# DIOT_signal_routing.net
KiCad netlist of a schematic drawn in Altium Designer
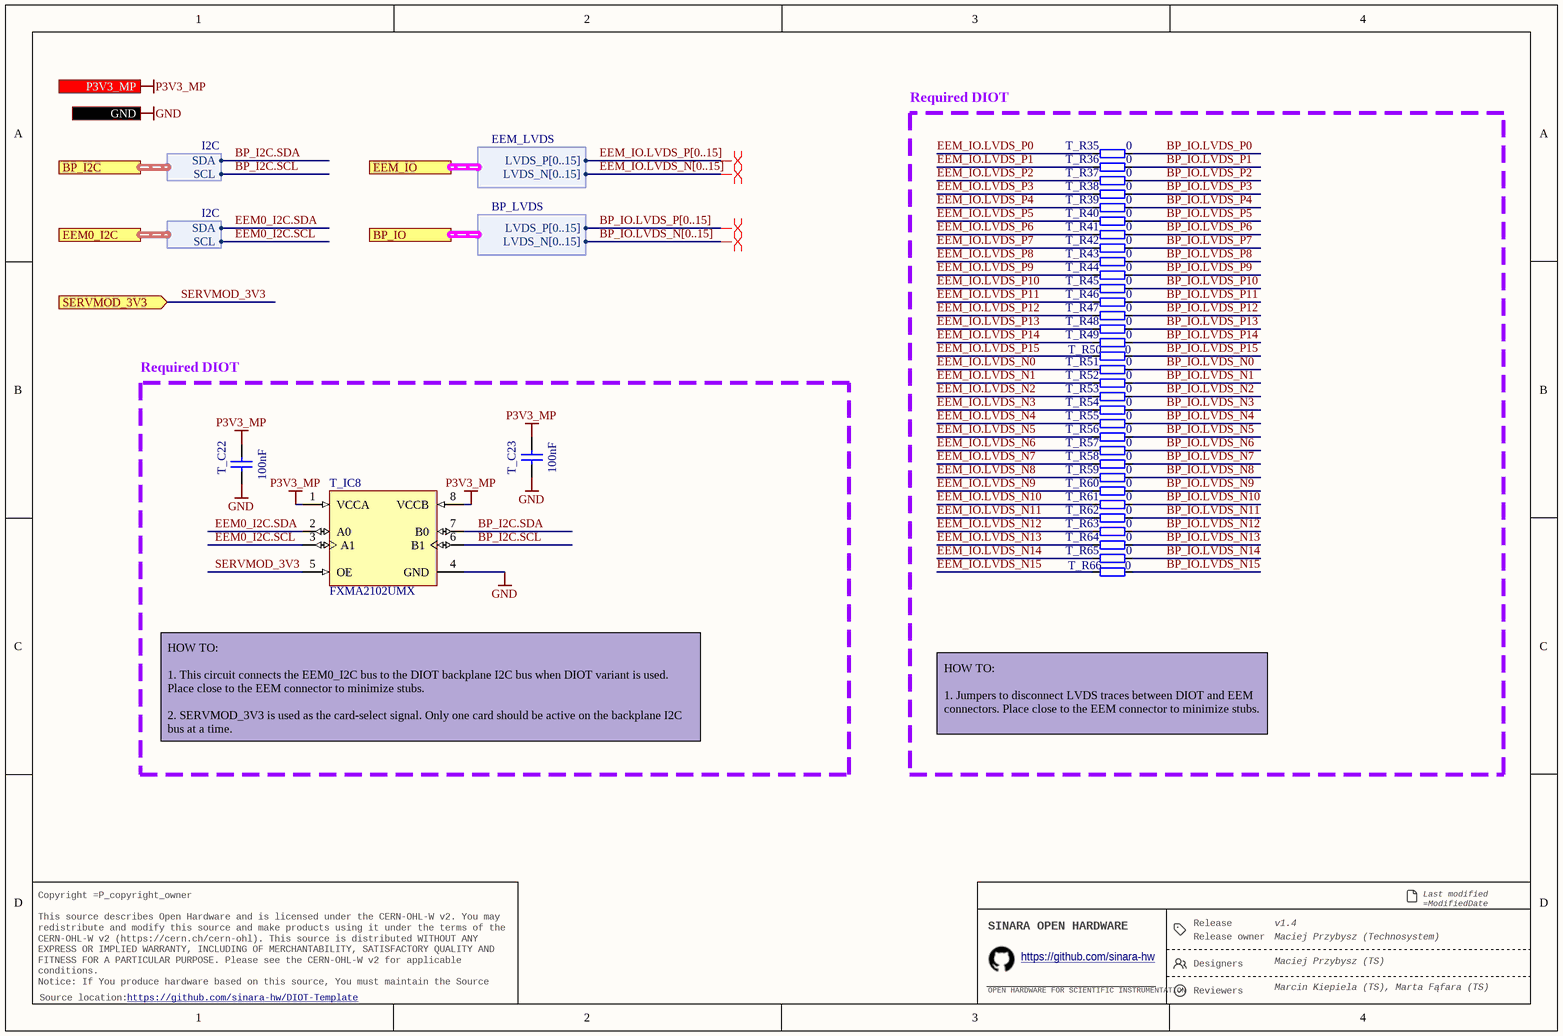
[diagram p0: DIOT_signal_routing.SchDoc]

(export (version "E")
  (design (tool "Eeschema 10.0.6"))
  (components
    (comp (ref "T_C22")
      (value "100nF")
      (footprint "CAPC1005X55N")
      (description "Non-polarised capacitor")
      (fields
        (field (name "PART NUMBER") "CC0402_100NF_50V_10%_X7R")
        (field (name "VOLTAGE") "50V")
        (field (name "AUTHOR") "CERN DEM MR")
      )
      (libsource (lib "Capacitors") (part "Capacitor - non polarized"))
    )
    (comp (ref "T_C23")
      (value "100nF")
      (footprint "CAPC1005X55N")
      (description "Non-polarised capacitor")
      (fields
        (field (name "PART NUMBER") "CC0402_100NF_50V_10%_X7R")
        (field (name "VOLTAGE") "50V")
        (field (name "AUTHOR") "CERN DEM MR")
      )
      (libsource (lib "Capacitors") (part "Capacitor - non polarized"))
    )
    (comp (ref "T_IC8")
      (value "FXMA2102UMX")
      (footprint "FXMA2102UMX")
      (description "Dual Supply 2-Bit Voltage Translator/Buffer/Repeater Isolator for I2C Applications")
      (fields (field (name "MANUFACTURER") "Onsemi"))
      (libsource (lib "TechnoSystem Workspace") (part "FXMA2102UMX"))
    )
    (comp (ref "T_R35")
      (value "0")
      (footprint "RESC1005X40N")
      (description "Resistor")
      (fields
        (field (name "PART NUMBER") "R0402_0R_JUMPER")
        (field (name "MANUFACTURER") "GENERIC")
        (field (name "AUTHOR") "CERN DEM JLC")
      )
      (libsource (lib "Resistors") (part "Resistor"))
    )
    (comp (ref "T_R36")
      (value "0")
      (footprint "RESC1005X40N")
      (description "Resistor")
      (fields
        (field (name "PART NUMBER") "R0402_0R_JUMPER")
        (field (name "MANUFACTURER") "GENERIC")
        (field (name "AUTHOR") "CERN DEM JLC")
      )
      (libsource (lib "Resistors") (part "Resistor"))
    )
    (comp (ref "T_R37")
      (value "0")
      (footprint "RESC1005X40N")
      (description "Resistor")
      (fields
        (field (name "PART NUMBER") "R0402_0R_JUMPER")
        (field (name "MANUFACTURER") "GENERIC")
        (field (name "AUTHOR") "CERN DEM JLC")
      )
      (libsource (lib "Resistors") (part "Resistor"))
    )
    (comp (ref "T_R38")
      (value "0")
      (footprint "RESC1005X40N")
      (description "Resistor")
      (fields
        (field (name "PART NUMBER") "R0402_0R_JUMPER")
        (field (name "MANUFACTURER") "GENERIC")
        (field (name "AUTHOR") "CERN DEM JLC")
      )
      (libsource (lib "Resistors") (part "Resistor"))
    )
    (comp (ref "T_R39")
      (value "0")
      (footprint "RESC1005X40N")
      (description "Resistor")
      (fields
        (field (name "PART NUMBER") "R0402_0R_JUMPER")
        (field (name "MANUFACTURER") "GENERIC")
        (field (name "AUTHOR") "CERN DEM JLC")
      )
      (libsource (lib "Resistors") (part "Resistor"))
    )
    (comp (ref "T_R40")
      (value "0")
      (footprint "RESC1005X40N")
      (description "Resistor")
      (fields
        (field (name "PART NUMBER") "R0402_0R_JUMPER")
        (field (name "MANUFACTURER") "GENERIC")
        (field (name "AUTHOR") "CERN DEM JLC")
      )
      (libsource (lib "Resistors") (part "Resistor"))
    )
    (comp (ref "T_R41")
      (value "0")
      (footprint "RESC1005X40N")
      (description "Resistor")
      (fields
        (field (name "PART NUMBER") "R0402_0R_JUMPER")
        (field (name "MANUFACTURER") "GENERIC")
        (field (name "AUTHOR") "CERN DEM JLC")
      )
      (libsource (lib "Resistors") (part "Resistor"))
    )
    (comp (ref "T_R42")
      (value "0")
      (footprint "RESC1005X40N")
      (description "Resistor")
      (fields
        (field (name "PART NUMBER") "R0402_0R_JUMPER")
        (field (name "MANUFACTURER") "GENERIC")
        (field (name "AUTHOR") "CERN DEM JLC")
      )
      (libsource (lib "Resistors") (part "Resistor"))
    )
    (comp (ref "T_R43")
      (value "0")
      (footprint "RESC1005X40N")
      (description "Resistor")
      (fields
        (field (name "PART NUMBER") "R0402_0R_JUMPER")
        (field (name "MANUFACTURER") "GENERIC")
        (field (name "AUTHOR") "CERN DEM JLC")
      )
      (libsource (lib "Resistors") (part "Resistor"))
    )
    (comp (ref "T_R44")
      (value "0")
      (footprint "RESC1005X40N")
      (description "Resistor")
      (fields
        (field (name "PART NUMBER") "R0402_0R_JUMPER")
        (field (name "MANUFACTURER") "GENERIC")
        (field (name "AUTHOR") "CERN DEM JLC")
      )
      (libsource (lib "Resistors") (part "Resistor"))
    )
    (comp (ref "T_R45")
      (value "0")
      (footprint "RESC1005X40N")
      (description "Resistor")
      (fields
        (field (name "PART NUMBER") "R0402_0R_JUMPER")
        (field (name "MANUFACTURER") "GENERIC")
        (field (name "AUTHOR") "CERN DEM JLC")
      )
      (libsource (lib "Resistors") (part "Resistor"))
    )
    (comp (ref "T_R46")
      (value "0")
      (footprint "RESC1005X40N")
      (description "Resistor")
      (fields
        (field (name "PART NUMBER") "R0402_0R_JUMPER")
        (field (name "MANUFACTURER") "GENERIC")
        (field (name "AUTHOR") "CERN DEM JLC")
      )
      (libsource (lib "Resistors") (part "Resistor"))
    )
    (comp (ref "T_R47")
      (value "0")
      (footprint "RESC1005X40N")
      (description "Resistor")
      (fields
        (field (name "PART NUMBER") "R0402_0R_JUMPER")
        (field (name "MANUFACTURER") "GENERIC")
        (field (name "AUTHOR") "CERN DEM JLC")
      )
      (libsource (lib "Resistors") (part "Resistor"))
    )
    (comp (ref "T_R48")
      (value "0")
      (footprint "RESC1005X40N")
      (description "Resistor")
      (fields
        (field (name "PART NUMBER") "R0402_0R_JUMPER")
        (field (name "MANUFACTURER") "GENERIC")
        (field (name "AUTHOR") "CERN DEM JLC")
      )
      (libsource (lib "Resistors") (part "Resistor"))
    )
    (comp (ref "T_R49")
      (value "0")
      (footprint "RESC1005X40N")
      (description "Resistor")
      (fields
        (field (name "PART NUMBER") "R0402_0R_JUMPER")
        (field (name "MANUFACTURER") "GENERIC")
        (field (name "AUTHOR") "CERN DEM JLC")
      )
      (libsource (lib "Resistors") (part "Resistor"))
    )
    (comp (ref "T_R50")
      (value "0")
      (footprint "RESC1005X40N")
      (description "Resistor")
      (fields
        (field (name "PART NUMBER") "R0402_0R_JUMPER")
        (field (name "MANUFACTURER") "GENERIC")
        (field (name "AUTHOR") "CERN DEM JLC")
      )
      (libsource (lib "Resistors") (part "Resistor"))
    )
    (comp (ref "T_R51")
      (value "0")
      (footprint "RESC1005X40N")
      (description "Resistor")
      (fields
        (field (name "PART NUMBER") "R0402_0R_JUMPER")
        (field (name "MANUFACTURER") "GENERIC")
        (field (name "AUTHOR") "CERN DEM JLC")
      )
      (libsource (lib "Resistors") (part "Resistor"))
    )
    (comp (ref "T_R52")
      (value "0")
      (footprint "RESC1005X40N")
      (description "Resistor")
      (fields
        (field (name "PART NUMBER") "R0402_0R_JUMPER")
        (field (name "MANUFACTURER") "GENERIC")
        (field (name "AUTHOR") "CERN DEM JLC")
      )
      (libsource (lib "Resistors") (part "Resistor"))
    )
    (comp (ref "T_R53")
      (value "0")
      (footprint "RESC1005X40N")
      (description "Resistor")
      (fields
        (field (name "PART NUMBER") "R0402_0R_JUMPER")
        (field (name "MANUFACTURER") "GENERIC")
        (field (name "AUTHOR") "CERN DEM JLC")
      )
      (libsource (lib "Resistors") (part "Resistor"))
    )
    (comp (ref "T_R54")
      (value "0")
      (footprint "RESC1005X40N")
      (description "Resistor")
      (fields
        (field (name "PART NUMBER") "R0402_0R_JUMPER")
        (field (name "MANUFACTURER") "GENERIC")
        (field (name "AUTHOR") "CERN DEM JLC")
      )
      (libsource (lib "Resistors") (part "Resistor"))
    )
    (comp (ref "T_R55")
      (value "0")
      (footprint "RESC1005X40N")
      (description "Resistor")
      (fields
        (field (name "PART NUMBER") "R0402_0R_JUMPER")
        (field (name "MANUFACTURER") "GENERIC")
        (field (name "AUTHOR") "CERN DEM JLC")
      )
      (libsource (lib "Resistors") (part "Resistor"))
    )
    (comp (ref "T_R56")
      (value "0")
      (footprint "RESC1005X40N")
      (description "Resistor")
      (fields
        (field (name "PART NUMBER") "R0402_0R_JUMPER")
        (field (name "MANUFACTURER") "GENERIC")
        (field (name "AUTHOR") "CERN DEM JLC")
      )
      (libsource (lib "Resistors") (part "Resistor"))
    )
    (comp (ref "T_R57")
      (value "0")
      (footprint "RESC1005X40N")
      (description "Resistor")
      (fields
        (field (name "PART NUMBER") "R0402_0R_JUMPER")
        (field (name "MANUFACTURER") "GENERIC")
        (field (name "AUTHOR") "CERN DEM JLC")
      )
      (libsource (lib "Resistors") (part "Resistor"))
    )
    (comp (ref "T_R58")
      (value "0")
      (footprint "RESC1005X40N")
      (description "Resistor")
      (fields
        (field (name "PART NUMBER") "R0402_0R_JUMPER")
        (field (name "MANUFACTURER") "GENERIC")
        (field (name "AUTHOR") "CERN DEM JLC")
      )
      (libsource (lib "Resistors") (part "Resistor"))
    )
    (comp (ref "T_R59")
      (value "0")
      (footprint "RESC1005X40N")
      (description "Resistor")
      (fields
        (field (name "PART NUMBER") "R0402_0R_JUMPER")
        (field (name "MANUFACTURER") "GENERIC")
        (field (name "AUTHOR") "CERN DEM JLC")
      )
      (libsource (lib "Resistors") (part "Resistor"))
    )
    (comp (ref "T_R60")
      (value "0")
      (footprint "RESC1005X40N")
      (description "Resistor")
      (fields
        (field (name "PART NUMBER") "R0402_0R_JUMPER")
        (field (name "MANUFACTURER") "GENERIC")
        (field (name "AUTHOR") "CERN DEM JLC")
      )
      (libsource (lib "Resistors") (part "Resistor"))
    )
    (comp (ref "T_R61")
      (value "0")
      (footprint "RESC1005X40N")
      (description "Resistor")
      (fields
        (field (name "PART NUMBER") "R0402_0R_JUMPER")
        (field (name "MANUFACTURER") "GENERIC")
        (field (name "AUTHOR") "CERN DEM JLC")
      )
      (libsource (lib "Resistors") (part "Resistor"))
    )
    (comp (ref "T_R62")
      (value "0")
      (footprint "RESC1005X40N")
      (description "Resistor")
      (fields
        (field (name "PART NUMBER") "R0402_0R_JUMPER")
        (field (name "MANUFACTURER") "GENERIC")
        (field (name "AUTHOR") "CERN DEM JLC")
      )
      (libsource (lib "Resistors") (part "Resistor"))
    )
    (comp (ref "T_R63")
      (value "0")
      (footprint "RESC1005X40N")
      (description "Resistor")
      (fields
        (field (name "PART NUMBER") "R0402_0R_JUMPER")
        (field (name "MANUFACTURER") "GENERIC")
        (field (name "AUTHOR") "CERN DEM JLC")
      )
      (libsource (lib "Resistors") (part "Resistor"))
    )
    (comp (ref "T_R64")
      (value "0")
      (footprint "RESC1005X40N")
      (description "Resistor")
      (fields
        (field (name "PART NUMBER") "R0402_0R_JUMPER")
        (field (name "MANUFACTURER") "GENERIC")
        (field (name "AUTHOR") "CERN DEM JLC")
      )
      (libsource (lib "Resistors") (part "Resistor"))
    )
    (comp (ref "T_R65")
      (value "0")
      (footprint "RESC1005X40N")
      (description "Resistor")
      (fields
        (field (name "PART NUMBER") "R0402_0R_JUMPER")
        (field (name "MANUFACTURER") "GENERIC")
        (field (name "AUTHOR") "CERN DEM JLC")
      )
      (libsource (lib "Resistors") (part "Resistor"))
    )
    (comp (ref "T_R66")
      (value "0")
      (footprint "RESC1005X40N")
      (description "Resistor")
      (fields
        (field (name "PART NUMBER") "R0402_0R_JUMPER")
        (field (name "MANUFACTURER") "GENERIC")
        (field (name "AUTHOR") "CERN DEM JLC")
      )
      (libsource (lib "Resistors") (part "Resistor"))
    )
  )
  (nets
    (net (code "4") (name "/BP_I2C.SCL") (class "Default")
      (node (ref "T_IC8") (pin "6") (pinfunction "B1_6") (pintype "bidirectional"))
    )
    (net (code "5") (name "/BP_I2C.SDA") (class "Default")
      (node (ref "T_IC8") (pin "7") (pinfunction "B0_7") (pintype "bidirectional"))
    )
    (net (code "6") (name "/BP_IO.LVDS_N0") (class "Default")
      (node (ref "T_R51") (pin "1") (pinfunction "1_1") (pintype "passive"))
    )
    (net (code "7") (name "/BP_IO.LVDS_N1") (class "Default")
      (node (ref "T_R52") (pin "1") (pinfunction "1_1") (pintype "passive"))
    )
    (net (code "8") (name "/BP_IO.LVDS_N2") (class "Default")
      (node (ref "T_R53") (pin "1") (pinfunction "1_1") (pintype "passive"))
    )
    (net (code "9") (name "/BP_IO.LVDS_N3") (class "Default")
      (node (ref "T_R54") (pin "1") (pinfunction "1_1") (pintype "passive"))
    )
    (net (code "10") (name "/BP_IO.LVDS_N4") (class "Default")
      (node (ref "T_R55") (pin "1") (pinfunction "1_1") (pintype "passive"))
    )
    (net (code "11") (name "/BP_IO.LVDS_N5") (class "Default")
      (node (ref "T_R56") (pin "1") (pinfunction "1_1") (pintype "passive"))
    )
    (net (code "12") (name "/BP_IO.LVDS_N6") (class "Default")
      (node (ref "T_R57") (pin "1") (pinfunction "1_1") (pintype "passive"))
    )
    (net (code "13") (name "/BP_IO.LVDS_N7") (class "Default")
      (node (ref "T_R58") (pin "1") (pinfunction "1_1") (pintype "passive"))
    )
    (net (code "14") (name "/BP_IO.LVDS_N8") (class "Default")
      (node (ref "T_R59") (pin "1") (pinfunction "1_1") (pintype "passive"))
    )
    (net (code "15") (name "/BP_IO.LVDS_N9") (class "Default")
      (node (ref "T_R60") (pin "1") (pinfunction "1_1") (pintype "passive"))
    )
    (net (code "16") (name "/BP_IO.LVDS_N10") (class "Default")
      (node (ref "T_R61") (pin "1") (pinfunction "1_1") (pintype "passive"))
    )
    (net (code "17") (name "/BP_IO.LVDS_N11") (class "Default")
      (node (ref "T_R62") (pin "1") (pinfunction "1_1") (pintype "passive"))
    )
    (net (code "18") (name "/BP_IO.LVDS_N12") (class "Default")
      (node (ref "T_R63") (pin "1") (pinfunction "1_1") (pintype "passive"))
    )
    (net (code "19") (name "/BP_IO.LVDS_N13") (class "Default")
      (node (ref "T_R64") (pin "1") (pinfunction "1_1") (pintype "passive"))
    )
    (net (code "20") (name "/BP_IO.LVDS_N14") (class "Default")
      (node (ref "T_R65") (pin "1") (pinfunction "1_1") (pintype "passive"))
    )
    (net (code "21") (name "/BP_IO.LVDS_N15") (class "Default")
      (node (ref "T_R66") (pin "2") (pinfunction "2_2") (pintype "passive"))
    )
    (net (code "22") (name "/BP_IO.LVDS_P0") (class "Default")
      (node (ref "T_R35") (pin "1") (pinfunction "1_1") (pintype "passive"))
    )
    (net (code "23") (name "/BP_IO.LVDS_P1") (class "Default")
      (node (ref "T_R36") (pin "1") (pinfunction "1_1") (pintype "passive"))
    )
    (net (code "24") (name "/BP_IO.LVDS_P2") (class "Default")
      (node (ref "T_R37") (pin "1") (pinfunction "1_1") (pintype "passive"))
    )
    (net (code "25") (name "/BP_IO.LVDS_P3") (class "Default")
      (node (ref "T_R38") (pin "1") (pinfunction "1_1") (pintype "passive"))
    )
    (net (code "26") (name "/BP_IO.LVDS_P4") (class "Default")
      (node (ref "T_R39") (pin "1") (pinfunction "1_1") (pintype "passive"))
    )
    (net (code "27") (name "/BP_IO.LVDS_P5") (class "Default")
      (node (ref "T_R40") (pin "1") (pinfunction "1_1") (pintype "passive"))
    )
    (net (code "28") (name "/BP_IO.LVDS_P6") (class "Default")
      (node (ref "T_R41") (pin "1") (pinfunction "1_1") (pintype "passive"))
    )
    (net (code "29") (name "/BP_IO.LVDS_P7") (class "Default")
      (node (ref "T_R42") (pin "1") (pinfunction "1_1") (pintype "passive"))
    )
    (net (code "30") (name "/BP_IO.LVDS_P8") (class "Default")
      (node (ref "T_R43") (pin "1") (pinfunction "1_1") (pintype "passive"))
    )
    (net (code "31") (name "/BP_IO.LVDS_P9") (class "Default")
      (node (ref "T_R44") (pin "1") (pinfunction "1_1") (pintype "passive"))
    )
    (net (code "32") (name "/BP_IO.LVDS_P10") (class "Default")
      (node (ref "T_R45") (pin "1") (pinfunction "1_1") (pintype "passive"))
    )
    (net (code "33") (name "/BP_IO.LVDS_P11") (class "Default")
      (node (ref "T_R46") (pin "1") (pinfunction "1_1") (pintype "passive"))
    )
    (net (code "34") (name "/BP_IO.LVDS_P12") (class "Default")
      (node (ref "T_R47") (pin "1") (pinfunction "1_1") (pintype "passive"))
    )
    (net (code "35") (name "/BP_IO.LVDS_P13") (class "Default")
      (node (ref "T_R48") (pin "1") (pinfunction "1_1") (pintype "passive"))
    )
    (net (code "36") (name "/BP_IO.LVDS_P14") (class "Default")
      (node (ref "T_R49") (pin "1") (pinfunction "1_1") (pintype "passive"))
    )
    (net (code "37") (name "/BP_IO.LVDS_P15") (class "Default")
      (node (ref "T_R50") (pin "2") (pinfunction "2_2") (pintype "passive"))
    )
    (net (code "40") (name "/EEM0_I2C.SCL") (class "Default")
      (node (ref "T_IC8") (pin "3") (pinfunction "A1_3") (pintype "bidirectional"))
    )
    (net (code "41") (name "/EEM0_I2C.SDA") (class "Default")
      (node (ref "T_IC8") (pin "2") (pinfunction "A0_2") (pintype "bidirectional"))
    )
    (net (code "42") (name "/EEM_IO.LVDS_N0") (class "Default")
      (node (ref "T_R51") (pin "2") (pinfunction "2_2") (pintype "passive"))
    )
    (net (code "43") (name "/EEM_IO.LVDS_N1") (class "Default")
      (node (ref "T_R52") (pin "2") (pinfunction "2_2") (pintype "passive"))
    )
    (net (code "44") (name "/EEM_IO.LVDS_N2") (class "Default")
      (node (ref "T_R53") (pin "2") (pinfunction "2_2") (pintype "passive"))
    )
    (net (code "45") (name "/EEM_IO.LVDS_N3") (class "Default")
      (node (ref "T_R54") (pin "2") (pinfunction "2_2") (pintype "passive"))
    )
    (net (code "46") (name "/EEM_IO.LVDS_N4") (class "Default")
      (node (ref "T_R55") (pin "2") (pinfunction "2_2") (pintype "passive"))
    )
    (net (code "47") (name "/EEM_IO.LVDS_N5") (class "Default")
      (node (ref "T_R56") (pin "2") (pinfunction "2_2") (pintype "passive"))
    )
    (net (code "48") (name "/EEM_IO.LVDS_N6") (class "Default")
      (node (ref "T_R57") (pin "2") (pinfunction "2_2") (pintype "passive"))
    )
    (net (code "49") (name "/EEM_IO.LVDS_N7") (class "Default")
      (node (ref "T_R58") (pin "2") (pinfunction "2_2") (pintype "passive"))
    )
    (net (code "50") (name "/EEM_IO.LVDS_N8") (class "Default")
      (node (ref "T_R59") (pin "2") (pinfunction "2_2") (pintype "passive"))
    )
    (net (code "51") (name "/EEM_IO.LVDS_N9") (class "Default")
      (node (ref "T_R60") (pin "2") (pinfunction "2_2") (pintype "passive"))
    )
    (net (code "52") (name "/EEM_IO.LVDS_N10") (class "Default")
      (node (ref "T_R61") (pin "2") (pinfunction "2_2") (pintype "passive"))
    )
    (net (code "53") (name "/EEM_IO.LVDS_N11") (class "Default")
      (node (ref "T_R62") (pin "2") (pinfunction "2_2") (pintype "passive"))
    )
    (net (code "54") (name "/EEM_IO.LVDS_N12") (class "Default")
      (node (ref "T_R63") (pin "2") (pinfunction "2_2") (pintype "passive"))
    )
    (net (code "55") (name "/EEM_IO.LVDS_N13") (class "Default")
      (node (ref "T_R64") (pin "2") (pinfunction "2_2") (pintype "passive"))
    )
    (net (code "56") (name "/EEM_IO.LVDS_N14") (class "Default")
      (node (ref "T_R65") (pin "2") (pinfunction "2_2") (pintype "passive"))
    )
    (net (code "57") (name "/EEM_IO.LVDS_N15") (class "Default")
      (node (ref "T_R66") (pin "1") (pinfunction "1_1") (pintype "passive"))
    )
    (net (code "58") (name "/EEM_IO.LVDS_P0") (class "Default")
      (node (ref "T_R35") (pin "2") (pinfunction "2_2") (pintype "passive"))
    )
    (net (code "59") (name "/EEM_IO.LVDS_P1") (class "Default")
      (node (ref "T_R36") (pin "2") (pinfunction "2_2") (pintype "passive"))
    )
    (net (code "60") (name "/EEM_IO.LVDS_P2") (class "Default")
      (node (ref "T_R37") (pin "2") (pinfunction "2_2") (pintype "passive"))
    )
    (net (code "61") (name "/EEM_IO.LVDS_P3") (class "Default")
      (node (ref "T_R38") (pin "2") (pinfunction "2_2") (pintype "passive"))
    )
    (net (code "62") (name "/EEM_IO.LVDS_P4") (class "Default")
      (node (ref "T_R39") (pin "2") (pinfunction "2_2") (pintype "passive"))
    )
    (net (code "63") (name "/EEM_IO.LVDS_P5") (class "Default")
      (node (ref "T_R40") (pin "2") (pinfunction "2_2") (pintype "passive"))
    )
    (net (code "64") (name "/EEM_IO.LVDS_P6") (class "Default")
      (node (ref "T_R41") (pin "2") (pinfunction "2_2") (pintype "passive"))
    )
    (net (code "65") (name "/EEM_IO.LVDS_P7") (class "Default")
      (node (ref "T_R42") (pin "2") (pinfunction "2_2") (pintype "passive"))
    )
    (net (code "66") (name "/EEM_IO.LVDS_P8") (class "Default")
      (node (ref "T_R43") (pin "2") (pinfunction "2_2") (pintype "passive"))
    )
    (net (code "67") (name "/EEM_IO.LVDS_P9") (class "Default")
      (node (ref "T_R44") (pin "2") (pinfunction "2_2") (pintype "passive"))
    )
    (net (code "68") (name "/EEM_IO.LVDS_P10") (class "Default")
      (node (ref "T_R45") (pin "2") (pinfunction "2_2") (pintype "passive"))
    )
    (net (code "69") (name "/EEM_IO.LVDS_P11") (class "Default")
      (node (ref "T_R46") (pin "2") (pinfunction "2_2") (pintype "passive"))
    )
    (net (code "70") (name "/EEM_IO.LVDS_P12") (class "Default")
      (node (ref "T_R47") (pin "2") (pinfunction "2_2") (pintype "passive"))
    )
    (net (code "71") (name "/EEM_IO.LVDS_P13") (class "Default")
      (node (ref "T_R48") (pin "2") (pinfunction "2_2") (pintype "passive"))
    )
    (net (code "72") (name "/EEM_IO.LVDS_P14") (class "Default")
      (node (ref "T_R49") (pin "2") (pinfunction "2_2") (pintype "passive"))
    )
    (net (code "73") (name "/EEM_IO.LVDS_P15") (class "Default")
      (node (ref "T_R50") (pin "1") (pinfunction "1_1") (pintype "passive"))
    )
    (net (code "76") (name "/SERVMOD_3V3") (class "Default")
      (node (ref "T_IC8") (pin "5") (pinfunction "OE_5") (pintype "input"))
    )
    (net (code "78") (name "GND") (class "Default")
      (node (ref "T_C22") (pin "1") (pinfunction "1_1") (pintype "passive"))
      (node (ref "T_C23") (pin "1") (pinfunction "1_1") (pintype "passive"))
      (node (ref "T_IC8") (pin "4") (pinfunction "GND_4") (pintype "power_in"))
    )
    (net (code "79") (name "P3V3_MP") (class "Default")
      (node (ref "T_C22") (pin "2") (pinfunction "2_2") (pintype "passive"))
      (node (ref "T_C23") (pin "2") (pinfunction "2_2") (pintype "passive"))
      (node (ref "T_IC8") (pin "1") (pinfunction "VCCA_1") (pintype "input"))
      (node (ref "T_IC8") (pin "8") (pinfunction "VCCB_8") (pintype "input"))
    )
  )
)
